# MK.net
KiCad netlist of a schematic drawn in Altium Designer
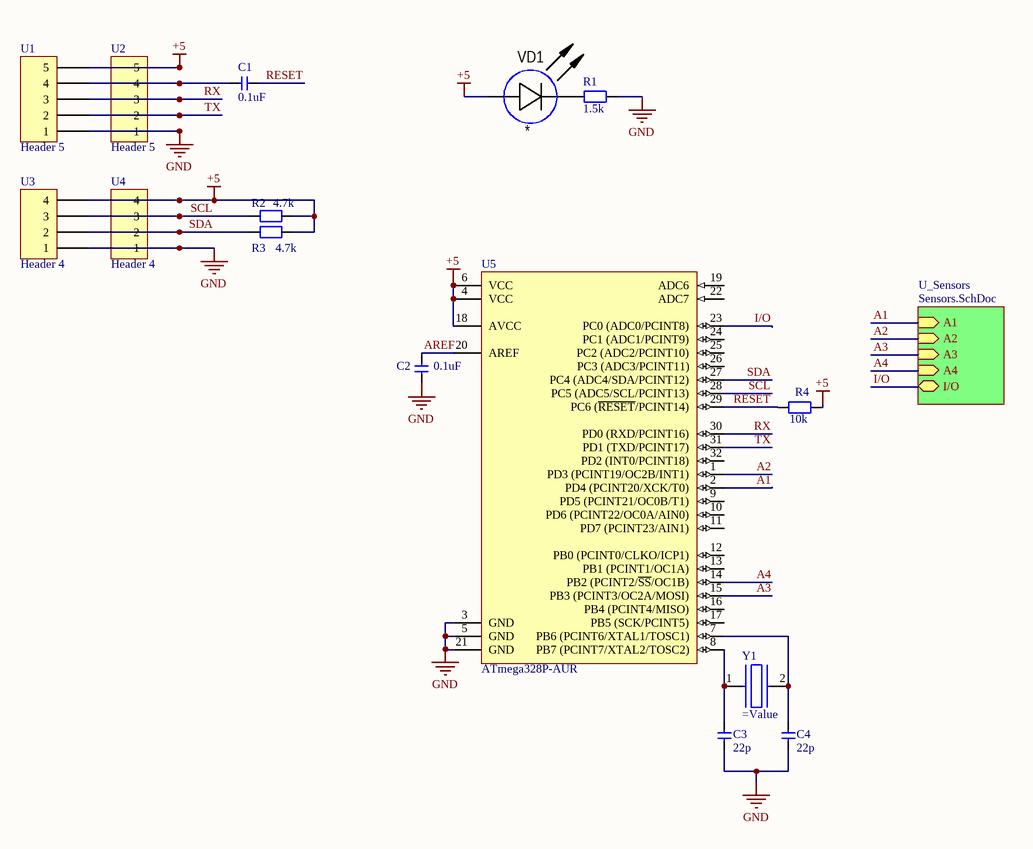
[diagram p0: MK.SchDoc]

(export (version "E")
  (design (tool "Eeschema 10.0.6"))
  (components
    (comp (ref "C1")
      (value "0.1uF")
      (footprint "cap0603")
      (libsource (lib "AlexChistiakov") (part "Cap SMD"))
    )
    (comp (ref "C2")
      (value "0.1uF")
      (footprint "cap0603")
      (libsource (lib "AlexChistiakov") (part "Cap SMD"))
    )
    (comp (ref "C3") (value "22p") (footprint "cap0603") (libsource (lib "AlexChistiakov") (part "Cap SMD")))
    (comp (ref "C4") (value "22p") (footprint "cap0603") (libsource (lib "AlexChistiakov") (part "Cap SMD")))
    (comp (ref "R1")
      (value "1.5k")
      (footprint "res0603")
      (libsource (lib "AlexChistiakov") (part "Resistor SMD"))
    )
    (comp (ref "R2")
      (value "4.7k")
      (footprint "res0603")
      (libsource (lib "AlexChistiakov") (part "Resistor SMD"))
    )
    (comp (ref "R3")
      (value "4.7k")
      (footprint "res0603")
      (libsource (lib "AlexChistiakov") (part "Resistor SMD"))
    )
    (comp (ref "R4")
      (value "10k")
      (footprint "res0603")
      (libsource (lib "AlexChistiakov") (part "Resistor SMD"))
    )
    (comp (ref "U1")
      (value "Header 5")
      (footprint "5x2.54")
      (libsource (lib "AlexChistiakov") (part "Header 5"))
    )
    (comp (ref "U2")
      (value "Header 5")
      (footprint "5x1.27")
      (libsource (lib "AlexChistiakov") (part "Header 5"))
    )
    (comp (ref "U3")
      (value "Header 4")
      (footprint "CON: PLS-4")
      (libsource (lib "AlexChistiakov") (part "Header 4"))
    )
    (comp (ref "U4")
      (value "Header 4")
      (footprint "4x1.25")
      (libsource (lib "AlexChistiakov") (part "Header 4"))
    )
    (comp (ref "U5")
      (value "ATmega328P-AUR")
      (footprint "32A_N")
      (fields (field (name "PUBLISHER") "Altium Limited"))
      (libsource (lib "Atmel Microcontroller 8-Bit megaAVR") (part "ATmega328P-AUR"))
    )
    (comp (ref "VD1") (value "*") (footprint "CH0603LB") (libsource (lib "Discrete") (part "LED")))
    (comp (ref "Y1")
      (value "~")
      (footprint "QSMD3.2x2.5_A")
      (libsource (lib "AlexChistiakov") (part "Quartz"))
    )
  )
  (nets
    (net (code "1") (name "+5") (class "Default")
      (node (ref "R2") (pin "2") (pinfunction "2_2") (pintype "passive"))
      (node (ref "R3") (pin "2") (pinfunction "2_2") (pintype "passive"))
      (node (ref "R4") (pin "2") (pinfunction "2_2") (pintype "passive"))
      (node (ref "U1") (pin "5") (pinfunction "5_5") (pintype "power_in"))
      (node (ref "U2") (pin "5") (pinfunction "5_5") (pintype "power_in"))
      (node (ref "U3") (pin "4") (pinfunction "4_4") (pintype "power_in"))
      (node (ref "U4") (pin "4") (pinfunction "4_4") (pintype "power_in"))
      (node (ref "U5") (pin "18") (pinfunction "AVCC_18") (pintype "power_in"))
      (node (ref "U5") (pin "4") (pinfunction "VCC_4") (pintype "power_in"))
      (node (ref "U5") (pin "6") (pinfunction "VCC_6") (pintype "power_in"))
      (node (ref "VD1") (pin "1") (pinfunction "A_1") (pintype "passive"))
    )
    (net (code "2") (name "/A1") (class "Default")
      (node (ref "U5") (pin "2") (pinfunction "PD4_(PCINT20/XCK/T0)_2") (pintype "bidirectional"))
    )
    (net (code "3") (name "/A2") (class "Default")
      (node (ref "U5") (pin "1") (pinfunction "PD3_(PCINT19/OC2B/INT1)_1") (pintype "bidirectional"))
    )
    (net (code "4") (name "/A3") (class "Default")
      (node (ref "U5") (pin "15") (pinfunction "PB3_(PCINT3/OC2A/MOSI)_15") (pintype "bidirectional"))
    )
    (net (code "5") (name "/A4") (class "Default")
      (node (ref "U5") (pin "14") (pinfunction "PB2_(PCINT2/~{SS}/OC1B)_14") (pintype "bidirectional"))
    )
    (net (code "6") (name "/AREF") (class "Default")
      (node (ref "C2") (pin "2") (pinfunction "2_2") (pintype "passive"))
      (node (ref "U5") (pin "20") (pinfunction "AREF_20") (pintype "passive"))
    )
    (net (code "7") (name "/I{slash}O") (class "Default")
      (node (ref "U5") (pin "23") (pinfunction "PC0_(ADC0/PCINT8)_23") (pintype "bidirectional"))
    )
    (net (code "8") (name "/RESET") (class "Default")
      (node (ref "C1") (pin "2") (pinfunction "2_2") (pintype "passive"))
      (node (ref "R4") (pin "1") (pinfunction "1_1") (pintype "passive"))
      (node (ref "U5") (pin "29") (pinfunction "PC6_(~{RESET}/PCINT14)_29") (pintype "bidirectional"))
    )
    (net (code "9") (name "/RX") (class "Default")
      (node (ref "U1") (pin "3") (pinfunction "3_3") (pintype "power_in"))
      (node (ref "U2") (pin "3") (pinfunction "3_3") (pintype "power_in"))
      (node (ref "U5") (pin "30") (pinfunction "PD0_(RXD/PCINT16)_30") (pintype "bidirectional"))
    )
    (net (code "10") (name "/SCL") (class "Default")
      (node (ref "R2") (pin "1") (pinfunction "1_1") (pintype "passive"))
      (node (ref "U3") (pin "3") (pinfunction "3_3") (pintype "power_in"))
      (node (ref "U4") (pin "3") (pinfunction "3_3") (pintype "power_in"))
      (node (ref "U5") (pin "28") (pinfunction "PC5_(ADC5/SCL/PCINT13)_28") (pintype "bidirectional"))
    )
    (net (code "11") (name "/SDA") (class "Default")
      (node (ref "R3") (pin "1") (pinfunction "1_1") (pintype "passive"))
      (node (ref "U3") (pin "2") (pinfunction "2_2") (pintype "power_in"))
      (node (ref "U4") (pin "2") (pinfunction "2_2") (pintype "power_in"))
      (node (ref "U5") (pin "27") (pinfunction "PC4_(ADC4/SDA/PCINT12)_27") (pintype "bidirectional"))
    )
    (net (code "12") (name "/TX") (class "Default")
      (node (ref "U1") (pin "2") (pinfunction "2_2") (pintype "power_in"))
      (node (ref "U2") (pin "2") (pinfunction "2_2") (pintype "power_in"))
      (node (ref "U5") (pin "31") (pinfunction "PD1_(TXD/PCINT17)_31") (pintype "bidirectional"))
    )
    (net (code "13") (name "GND") (class "Default")
      (node (ref "C2") (pin "1") (pinfunction "1_1") (pintype "passive"))
      (node (ref "C3") (pin "2") (pinfunction "2_2") (pintype "passive"))
      (node (ref "C4") (pin "2") (pinfunction "2_2") (pintype "passive"))
      (node (ref "R1") (pin "2") (pinfunction "2_2") (pintype "passive"))
      (node (ref "U1") (pin "1") (pinfunction "1_1") (pintype "power_in"))
      (node (ref "U2") (pin "1") (pinfunction "1_1") (pintype "power_in"))
      (node (ref "U3") (pin "1") (pinfunction "1_1") (pintype "power_in"))
      (node (ref "U4") (pin "1") (pinfunction "1_1") (pintype "power_in"))
      (node (ref "U5") (pin "21") (pinfunction "GND_21") (pintype "power_in"))
      (node (ref "U5") (pin "3") (pinfunction "GND_3") (pintype "power_in"))
      (node (ref "U5") (pin "5") (pinfunction "GND_5") (pintype "power_in"))
    )
    (net (code "14") (name "Net-(C1-Pad1)") (class "Default")
      (node (ref "C1") (pin "1") (pinfunction "1_1") (pintype "passive"))
      (node (ref "U1") (pin "4") (pinfunction "4_4") (pintype "power_in"))
      (node (ref "U2") (pin "4") (pinfunction "4_4") (pintype "power_in"))
    )
    (net (code "15") (name "Net-(U5-PB6_(PCINT6{slash}XTAL1{slash}TOSC1))") (class "Default")
      (node (ref "C4") (pin "1") (pinfunction "1_1") (pintype "passive"))
      (node (ref "U5") (pin "7") (pinfunction "PB6_(PCINT6/XTAL1/TOSC1)_7") (pintype "bidirectional"))
      (node (ref "Y1") (pin "2") (pintype "power_in"))
    )
    (net (code "16") (name "Net-(U5-PB7_(PCINT7{slash}XTAL2{slash}TOSC2))") (class "Default")
      (node (ref "C3") (pin "1") (pinfunction "1_1") (pintype "passive"))
      (node (ref "U5") (pin "8") (pinfunction "PB7_(PCINT7/XTAL2/TOSC2)_8") (pintype "bidirectional"))
      (node (ref "Y1") (pin "1") (pintype "power_in"))
    )
    (net (code "17") (name "Net-(VD1-C)") (class "Default")
      (node (ref "R1") (pin "1") (pinfunction "1_1") (pintype "passive"))
      (node (ref "VD1") (pin "2") (pinfunction "C_2") (pintype "passive"))
    )
    (net (code "18") (name "unconnected-(U5-ADC6-Pad19)") (class "Default")
      (node (ref "U5") (pin "19") (pinfunction "ADC6_19") (pintype "input"))
    )
    (net (code "19") (name "unconnected-(U5-ADC7-Pad22)") (class "Default")
      (node (ref "U5") (pin "22") (pinfunction "ADC7_22") (pintype "input"))
    )
    (net (code "20") (name "unconnected-(U5-PB0_(PCINT0{slash}CLKO{slash}ICP1)-Pad12)") (class "Default")
      (node (ref "U5") (pin "12") (pinfunction "PB0_(PCINT0/CLKO/ICP1)_12") (pintype "bidirectional"))
    )
    (net (code "21") (name "unconnected-(U5-PB1_(PCINT1{slash}OC1A)-Pad13)") (class "Default")
      (node (ref "U5") (pin "13") (pinfunction "PB1_(PCINT1/OC1A)_13") (pintype "bidirectional"))
    )
    (net (code "22") (name "unconnected-(U5-PB4_(PCINT4{slash}MISO)-Pad16)") (class "Default")
      (node (ref "U5") (pin "16") (pinfunction "PB4_(PCINT4/MISO)_16") (pintype "bidirectional"))
    )
    (net (code "23") (name "unconnected-(U5-PB5_(SCK{slash}PCINT5)-Pad17)") (class "Default")
      (node (ref "U5") (pin "17") (pinfunction "PB5_(SCK/PCINT5)_17") (pintype "bidirectional"))
    )
    (net (code "24") (name "unconnected-(U5-PC1_(ADC1{slash}PCINT9)-Pad24)") (class "Default")
      (node (ref "U5") (pin "24") (pinfunction "PC1_(ADC1/PCINT9)_24") (pintype "bidirectional"))
    )
    (net (code "25") (name "unconnected-(U5-PC2_(ADC2{slash}PCINT10)-Pad25)") (class "Default")
      (node (ref "U5") (pin "25") (pinfunction "PC2_(ADC2/PCINT10)_25") (pintype "bidirectional"))
    )
    (net (code "26") (name "unconnected-(U5-PC3_(ADC3{slash}PCINT11)-Pad26)") (class "Default")
      (node (ref "U5") (pin "26") (pinfunction "PC3_(ADC3/PCINT11)_26") (pintype "bidirectional"))
    )
    (net (code "27") (name "unconnected-(U5-PD2_(INT0{slash}PCINT18)-Pad32)") (class "Default")
      (node (ref "U5") (pin "32") (pinfunction "PD2_(INT0/PCINT18)_32") (pintype "bidirectional"))
    )
    (net (code "28") (name "unconnected-(U5-PD5_(PCINT21{slash}OC0B{slash}T1)-Pad9)") (class "Default")
      (node (ref "U5") (pin "9") (pinfunction "PD5_(PCINT21/OC0B/T1)_9") (pintype "bidirectional"))
    )
    (net (code "29") (name "unconnected-(U5-PD6_(PCINT22{slash}OC0A{slash}AIN0)-Pad10)") (class "Default")
      (node (ref "U5") (pin "10") (pinfunction "PD6_(PCINT22/OC0A/AIN0)_10") (pintype "bidirectional"))
    )
    (net (code "30") (name "unconnected-(U5-PD7_(PCINT23{slash}AIN1)-Pad11)") (class "Default")
      (node (ref "U5") (pin "11") (pinfunction "PD7_(PCINT23/AIN1)_11") (pintype "bidirectional"))
    )
  )
)
